# dic_deska.net
KiCad netlist of a schematic drawn in EAGLE
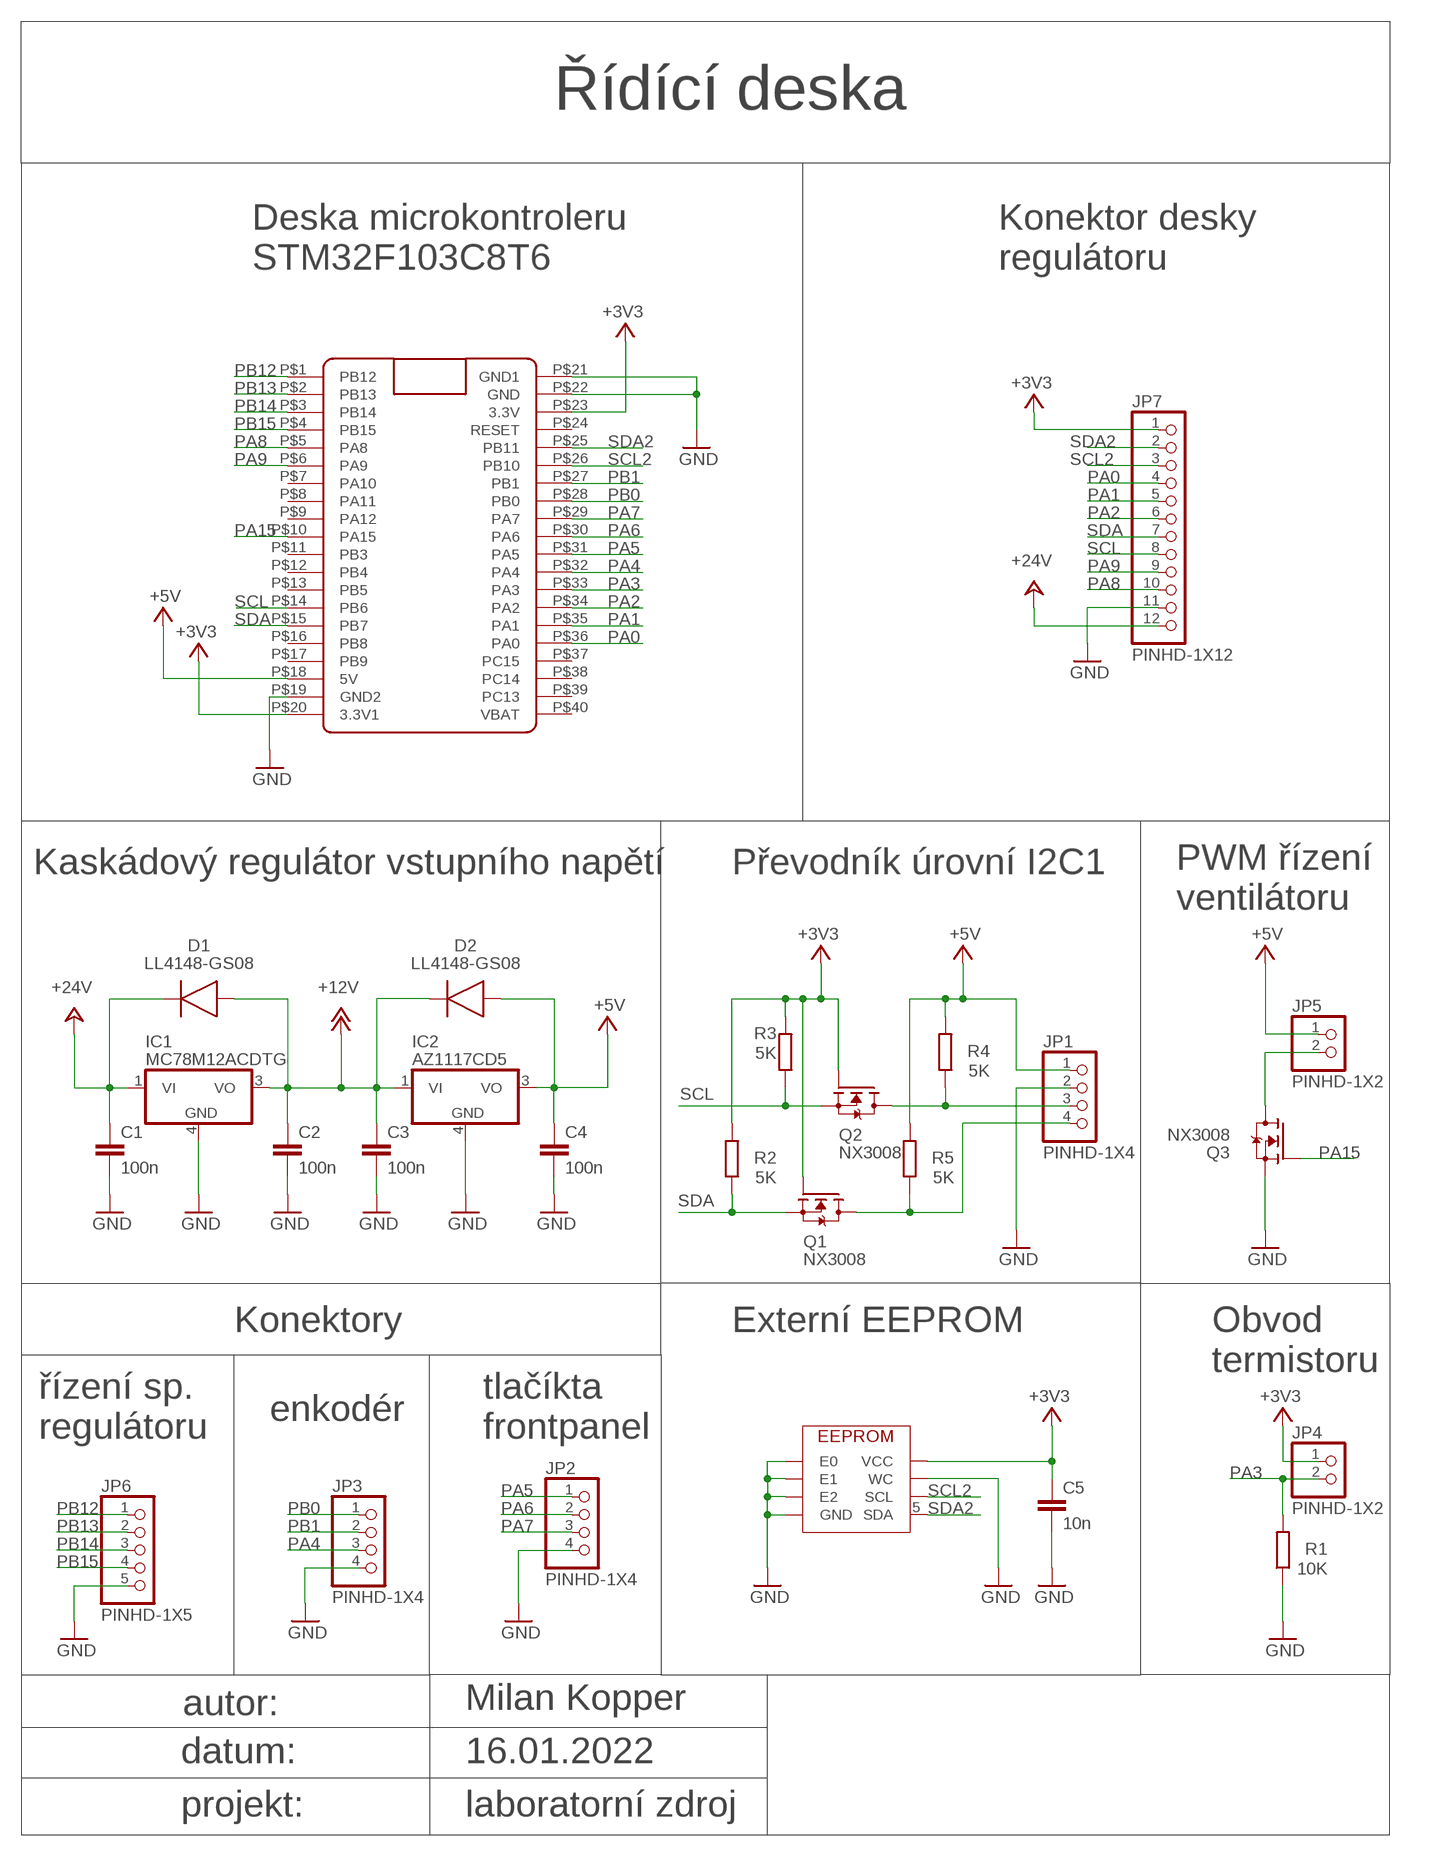
[diagram p0: schematic, sheet 1]

(export (version "E")
  (design (tool "Eeschema 10.0.6"))
  (components
    (comp (ref "C1")
      (value "100n")
      (footprint "eagle-import:C0805")
      (libsource (lib "eagle-import") (part "C-EUC0805"))
    )
    (comp (ref "C2")
      (value "100n")
      (footprint "eagle-import:C0805")
      (libsource (lib "eagle-import") (part "C-EUC0805"))
    )
    (comp (ref "C3")
      (value "100n")
      (footprint "eagle-import:C0805")
      (libsource (lib "eagle-import") (part "C-EUC0805"))
    )
    (comp (ref "C4")
      (value "100n")
      (footprint "eagle-import:C0805")
      (libsource (lib "eagle-import") (part "C-EUC0805"))
    )
    (comp (ref "C5")
      (value "10n")
      (footprint "eagle-import:C0805")
      (libsource (lib "eagle-import") (part "C-EUC0805"))
    )
    (comp (ref "D1")
      (value "LL4148-GS08")
      (footprint "eagle-import:DIOMELF3516")
      (fields (field (name "MANUFACTURER") "Vishay Semiconductor Diodes Division "))
      (libsource (lib "eagle-import") (part "DIODE__SOD-80LL4148-GS08"))
    )
    (comp (ref "D2")
      (value "LL4148-GS08")
      (footprint "eagle-import:DIOMELF3516")
      (fields (field (name "MANUFACTURER") "Vishay Semiconductor Diodes Division "))
      (libsource (lib "eagle-import") (part "DIODE__SOD-80LL4148-GS08"))
    )
    (comp (ref "IC1")
      (value "MC78M12ACDTG")
      (footprint "eagle-import:DPACK_3")
      (libsource (lib "eagle-import") (part "MC78M12BDTG"))
    )
    (comp (ref "IC2")
      (value "AZ1117CD5")
      (footprint "eagle-import:DPACK_3")
      (libsource (lib "eagle-import") (part "MC78M05CDTG"))
    )
    (comp (ref "JP1")
      (value "PINHD-1X4")
      (footprint "eagle-import:1X04")
      (libsource (lib "eagle-import") (part "PINHD-1X4"))
    )
    (comp (ref "JP2")
      (value "PINHD-1X4")
      (footprint "eagle-import:1X04")
      (libsource (lib "eagle-import") (part "PINHD-1X4"))
    )
    (comp (ref "JP3")
      (value "PINHD-1X4")
      (footprint "eagle-import:1X04")
      (libsource (lib "eagle-import") (part "PINHD-1X4"))
    )
    (comp (ref "JP4")
      (value "PINHD-1X2")
      (footprint "eagle-import:1X02")
      (libsource (lib "eagle-import") (part "PINHD-1X2"))
    )
    (comp (ref "JP5")
      (value "PINHD-1X2")
      (footprint "eagle-import:1X02")
      (libsource (lib "eagle-import") (part "PINHD-1X2"))
    )
    (comp (ref "JP6")
      (value "PINHD-1X5")
      (footprint "eagle-import:1X05")
      (libsource (lib "eagle-import") (part "PINHD-1X5"))
    )
    (comp (ref "JP7")
      (value "PINHD-1X12")
      (footprint "eagle-import:1X12")
      (libsource (lib "eagle-import") (part "PINHD-1X12"))
    )
    (comp (ref "Q1")
      (value "NX3008")
      (footprint "eagle-import:SOT95P240X110-3N")
      (libsource (lib "eagle-import") (part "NX3008"))
    )
    (comp (ref "Q2")
      (value "NX3008")
      (footprint "eagle-import:SOT95P240X110-3N")
      (libsource (lib "eagle-import") (part "NX3008"))
    )
    (comp (ref "Q3")
      (value "NX3008")
      (footprint "eagle-import:SOT95P240X110-3N")
      (libsource (lib "eagle-import") (part "NX3008"))
    )
    (comp (ref "R1")
      (value "10K")
      (footprint "eagle-import:R0805")
      (libsource (lib "eagle-import") (part "R-EU_R0805"))
    )
    (comp (ref "R2")
      (value "5K")
      (footprint "eagle-import:R0805")
      (libsource (lib "eagle-import") (part "R-EU_R0805"))
    )
    (comp (ref "R3")
      (value "5K")
      (footprint "eagle-import:R0805")
      (libsource (lib "eagle-import") (part "R-EU_R0805"))
    )
    (comp (ref "R4")
      (value "5K")
      (footprint "eagle-import:R0805")
      (libsource (lib "eagle-import") (part "R-EU_R0805"))
    )
    (comp (ref "R5")
      (value "5K")
      (footprint "eagle-import:R0805")
      (libsource (lib "eagle-import") (part "R-EU_R0805"))
    )
    (comp (ref "U$1")
      (value "BLUE_PILL")
      (footprint "eagle-import:BLUE_PILL")
      (libsource (lib "eagle-import") (part "BLUE_PILL"))
    )
    (comp (ref "U$2")
      (value "M24CXX")
      (footprint "eagle-import:SO8")
      (libsource (lib "eagle-import") (part "M24CXX"))
    )
  )
  (nets
    (net (code "1") (name "+3V3") (class "Default")
      (node (ref "C5") (pin "1") (pinfunction "1_1") (pintype "passive"))
      (node (ref "JP4") (pin "1") (pinfunction "1_1") (pintype "passive"))
      (node (ref "JP7") (pin "1") (pinfunction "1_1") (pintype "passive"))
      (node (ref "Q1") (pin "1") (pinfunction "G_1") (pintype "passive"))
      (node (ref "Q2") (pin "1") (pinfunction "G_1") (pintype "passive"))
      (node (ref "R2") (pin "2") (pinfunction "2_2") (pintype "passive"))
      (node (ref "R3") (pin "2") (pinfunction "2_2") (pintype "passive"))
      (node (ref "U$1") (pin "P$20") (pinfunction "3.3V1_P$20") (pintype "bidirectional"))
      (node (ref "U$1") (pin "P$23") (pinfunction "3.3V_P$23") (pintype "bidirectional"))
      (node (ref "U$2") (pin "8") (pinfunction "VCC_8") (pintype "bidirectional"))
    )
    (net (code "2") (name "+5V") (class "Default")
      (node (ref "C4") (pin "1") (pinfunction "1_1") (pintype "passive"))
      (node (ref "D2") (pin "2") (pinfunction "A_2") (pintype "passive"))
      (node (ref "IC2") (pin "3") (pinfunction "VO_3") (pintype "passive"))
      (node (ref "JP1") (pin "1") (pinfunction "1_1") (pintype "passive"))
      (node (ref "JP5") (pin "1") (pinfunction "1_1") (pintype "passive"))
      (node (ref "R4") (pin "2") (pinfunction "2_2") (pintype "passive"))
      (node (ref "R5") (pin "2") (pinfunction "2_2") (pintype "passive"))
      (node (ref "U$1") (pin "P$18") (pinfunction "5V_P$18") (pintype "bidirectional"))
    )
    (net (code "3") (name "+12V") (class "Default")
      (node (ref "C2") (pin "1") (pinfunction "1_1") (pintype "passive"))
      (node (ref "C3") (pin "1") (pinfunction "1_1") (pintype "passive"))
      (node (ref "D1") (pin "2") (pinfunction "A_2") (pintype "passive"))
      (node (ref "D2") (pin "1") (pinfunction "C_1") (pintype "passive"))
      (node (ref "IC1") (pin "3") (pinfunction "VO_3") (pintype "passive"))
      (node (ref "IC2") (pin "1") (pinfunction "VI_1") (pintype "input"))
    )
    (net (code "4") (name "+24V") (class "Default")
      (node (ref "C1") (pin "1") (pinfunction "1_1") (pintype "passive"))
      (node (ref "D1") (pin "1") (pinfunction "C_1") (pintype "passive"))
      (node (ref "IC1") (pin "1") (pinfunction "VI_1") (pintype "input"))
      (node (ref "JP7") (pin "12") (pinfunction "12_12") (pintype "passive"))
    )
    (net (code "5") (name "/PA0") (class "Default")
      (node (ref "JP7") (pin "4") (pinfunction "4_4") (pintype "passive"))
      (node (ref "U$1") (pin "P$36") (pinfunction "PA0_P$36") (pintype "bidirectional"))
    )
    (net (code "6") (name "/PA1") (class "Default")
      (node (ref "JP7") (pin "5") (pinfunction "5_5") (pintype "passive"))
      (node (ref "U$1") (pin "P$35") (pinfunction "PA1_P$35") (pintype "bidirectional"))
    )
    (net (code "7") (name "/PA2") (class "Default")
      (node (ref "JP7") (pin "6") (pinfunction "6_6") (pintype "passive"))
      (node (ref "U$1") (pin "P$34") (pinfunction "PA2_P$34") (pintype "bidirectional"))
    )
    (net (code "8") (name "/PA3") (class "Default")
      (node (ref "JP4") (pin "2") (pinfunction "2_2") (pintype "passive"))
      (node (ref "R1") (pin "2") (pinfunction "2_2") (pintype "passive"))
      (node (ref "U$1") (pin "P$33") (pinfunction "PA3_P$33") (pintype "bidirectional"))
    )
    (net (code "9") (name "/PA4") (class "Default")
      (node (ref "JP3") (pin "3") (pinfunction "3_3") (pintype "passive"))
      (node (ref "U$1") (pin "P$32") (pinfunction "PA4_P$32") (pintype "bidirectional"))
    )
    (net (code "10") (name "/PA5") (class "Default")
      (node (ref "JP2") (pin "1") (pinfunction "1_1") (pintype "passive"))
      (node (ref "U$1") (pin "P$31") (pinfunction "PA5_P$31") (pintype "bidirectional"))
    )
    (net (code "11") (name "/PA6") (class "Default")
      (node (ref "JP2") (pin "2") (pinfunction "2_2") (pintype "passive"))
      (node (ref "U$1") (pin "P$30") (pinfunction "PA6_P$30") (pintype "bidirectional"))
    )
    (net (code "12") (name "/PA7") (class "Default")
      (node (ref "JP2") (pin "3") (pinfunction "3_3") (pintype "passive"))
      (node (ref "U$1") (pin "P$29") (pinfunction "PA7_P$29") (pintype "bidirectional"))
    )
    (net (code "13") (name "/PA8") (class "Default")
      (node (ref "JP7") (pin "10") (pinfunction "10_10") (pintype "passive"))
      (node (ref "U$1") (pin "P$5") (pinfunction "PA8_P$5") (pintype "bidirectional"))
    )
    (net (code "14") (name "/PA9") (class "Default")
      (node (ref "JP7") (pin "9") (pinfunction "9_9") (pintype "passive"))
      (node (ref "U$1") (pin "P$6") (pinfunction "PA9_P$6") (pintype "bidirectional"))
    )
    (net (code "15") (name "/PA15") (class "Default")
      (node (ref "Q3") (pin "1") (pinfunction "G_1") (pintype "passive"))
      (node (ref "U$1") (pin "P$10") (pinfunction "PA15_P$10") (pintype "bidirectional"))
    )
    (net (code "16") (name "/PB0") (class "Default")
      (node (ref "JP3") (pin "1") (pinfunction "1_1") (pintype "passive"))
      (node (ref "U$1") (pin "P$28") (pinfunction "PB0_P$28") (pintype "bidirectional"))
    )
    (net (code "17") (name "/PB1") (class "Default")
      (node (ref "JP3") (pin "2") (pinfunction "2_2") (pintype "passive"))
      (node (ref "U$1") (pin "P$27") (pinfunction "PB1_P$27") (pintype "bidirectional"))
    )
    (net (code "18") (name "/PB12") (class "Default")
      (node (ref "JP6") (pin "1") (pinfunction "1_1") (pintype "passive"))
      (node (ref "U$1") (pin "P$1") (pinfunction "PB12_P$1") (pintype "bidirectional"))
    )
    (net (code "19") (name "/PB13") (class "Default")
      (node (ref "JP6") (pin "2") (pinfunction "2_2") (pintype "passive"))
      (node (ref "U$1") (pin "P$2") (pinfunction "PB13_P$2") (pintype "bidirectional"))
    )
    (net (code "20") (name "/PB14") (class "Default")
      (node (ref "JP6") (pin "3") (pinfunction "3_3") (pintype "passive"))
      (node (ref "U$1") (pin "P$3") (pinfunction "PB14_P$3") (pintype "bidirectional"))
    )
    (net (code "21") (name "/PB15") (class "Default")
      (node (ref "JP6") (pin "4") (pinfunction "4_4") (pintype "passive"))
      (node (ref "U$1") (pin "P$4") (pinfunction "PB15_P$4") (pintype "bidirectional"))
    )
    (net (code "22") (name "/SCL") (class "Default")
      (node (ref "JP7") (pin "8") (pinfunction "8_8") (pintype "passive"))
      (node (ref "Q2") (pin "2") (pinfunction "S_2") (pintype "passive"))
      (node (ref "R3") (pin "1") (pinfunction "1_1") (pintype "passive"))
      (node (ref "U$1") (pin "P$14") (pinfunction "PB6_P$14") (pintype "bidirectional"))
    )
    (net (code "23") (name "/SCL2") (class "Default")
      (node (ref "JP7") (pin "3") (pinfunction "3_3") (pintype "passive"))
      (node (ref "U$1") (pin "P$26") (pinfunction "PB10_P$26") (pintype "bidirectional"))
      (node (ref "U$2") (pin "6") (pinfunction "SCL_6") (pintype "bidirectional"))
    )
    (net (code "24") (name "/SDA") (class "Default")
      (node (ref "JP7") (pin "7") (pinfunction "7_7") (pintype "passive"))
      (node (ref "Q1") (pin "2") (pinfunction "S_2") (pintype "passive"))
      (node (ref "R2") (pin "1") (pinfunction "1_1") (pintype "passive"))
      (node (ref "U$1") (pin "P$15") (pinfunction "PB7_P$15") (pintype "bidirectional"))
    )
    (net (code "25") (name "/SDA2") (class "Default")
      (node (ref "JP7") (pin "2") (pinfunction "2_2") (pintype "passive"))
      (node (ref "U$1") (pin "P$25") (pinfunction "PB11_P$25") (pintype "bidirectional"))
      (node (ref "U$2") (pin "5") (pinfunction "SDA_5") (pintype "bidirectional"))
    )
    (net (code "26") (name "GND") (class "Default")
      (node (ref "C1") (pin "2") (pinfunction "2_2") (pintype "passive"))
      (node (ref "C2") (pin "2") (pinfunction "2_2") (pintype "passive"))
      (node (ref "C3") (pin "2") (pinfunction "2_2") (pintype "passive"))
      (node (ref "C4") (pin "2") (pinfunction "2_2") (pintype "passive"))
      (node (ref "C5") (pin "2") (pinfunction "2_2") (pintype "passive"))
      (node (ref "IC1") (pin "4") (pinfunction "GND_4") (pintype "passive"))
      (node (ref "IC2") (pin "4") (pinfunction "GND_4") (pintype "passive"))
      (node (ref "JP1") (pin "2") (pinfunction "2_2") (pintype "passive"))
      (node (ref "JP2") (pin "4") (pinfunction "4_4") (pintype "passive"))
      (node (ref "JP3") (pin "4") (pinfunction "4_4") (pintype "passive"))
      (node (ref "JP6") (pin "5") (pinfunction "5_5") (pintype "passive"))
      (node (ref "JP7") (pin "11") (pinfunction "11_11") (pintype "passive"))
      (node (ref "Q3") (pin "2") (pinfunction "S_2") (pintype "passive"))
      (node (ref "R1") (pin "1") (pinfunction "1_1") (pintype "passive"))
      (node (ref "U$1") (pin "P$19") (pinfunction "GND2_P$19") (pintype "bidirectional"))
      (node (ref "U$1") (pin "P$21") (pinfunction "GND1_P$21") (pintype "power_in"))
      (node (ref "U$1") (pin "P$22") (pinfunction "GND_P$22") (pintype "bidirectional"))
      (node (ref "U$2") (pin "1") (pinfunction "E0_1") (pintype "bidirectional"))
      (node (ref "U$2") (pin "2") (pinfunction "E1_2") (pintype "bidirectional"))
      (node (ref "U$2") (pin "3") (pinfunction "E2_3") (pintype "bidirectional"))
      (node (ref "U$2") (pin "4") (pinfunction "GND_4") (pintype "bidirectional"))
      (node (ref "U$2") (pin "7") (pinfunction "WC_7") (pintype "bidirectional"))
    )
    (net (code "27") (name "Net-(Q1-D)") (class "Default")
      (node (ref "JP1") (pin "4") (pinfunction "4_4") (pintype "passive"))
      (node (ref "Q1") (pin "3") (pinfunction "D_3") (pintype "passive"))
      (node (ref "R5") (pin "1") (pinfunction "1_1") (pintype "passive"))
    )
    (net (code "28") (name "Net-(Q2-D)") (class "Default")
      (node (ref "JP1") (pin "3") (pinfunction "3_3") (pintype "passive"))
      (node (ref "Q2") (pin "3") (pinfunction "D_3") (pintype "passive"))
      (node (ref "R4") (pin "1") (pinfunction "1_1") (pintype "passive"))
    )
    (net (code "29") (name "Net-(Q3-D)") (class "Default")
      (node (ref "JP5") (pin "2") (pinfunction "2_2") (pintype "passive"))
      (node (ref "Q3") (pin "3") (pinfunction "D_3") (pintype "passive"))
    )
    (net (code "30") (name "unconnected-(U$1-PA10-PadP$7)") (class "Default")
      (node (ref "U$1") (pin "P$7") (pinfunction "PA10_P$7") (pintype "bidirectional"))
    )
    (net (code "31") (name "unconnected-(U$1-PA11-PadP$8)") (class "Default")
      (node (ref "U$1") (pin "P$8") (pinfunction "PA11_P$8") (pintype "bidirectional"))
    )
    (net (code "32") (name "unconnected-(U$1-PA12-PadP$9)") (class "Default")
      (node (ref "U$1") (pin "P$9") (pinfunction "PA12_P$9") (pintype "bidirectional"))
    )
    (net (code "33") (name "unconnected-(U$1-PB3-PadP$11)") (class "Default")
      (node (ref "U$1") (pin "P$11") (pinfunction "PB3_P$11") (pintype "bidirectional"))
    )
    (net (code "34") (name "unconnected-(U$1-PB4-PadP$12)") (class "Default")
      (node (ref "U$1") (pin "P$12") (pinfunction "PB4_P$12") (pintype "bidirectional"))
    )
    (net (code "35") (name "unconnected-(U$1-PB5-PadP$13)") (class "Default")
      (node (ref "U$1") (pin "P$13") (pinfunction "PB5_P$13") (pintype "bidirectional"))
    )
    (net (code "36") (name "unconnected-(U$1-PB8-PadP$16)") (class "Default")
      (node (ref "U$1") (pin "P$16") (pinfunction "PB8_P$16") (pintype "bidirectional"))
    )
    (net (code "37") (name "unconnected-(U$1-PB9-PadP$17)") (class "Default")
      (node (ref "U$1") (pin "P$17") (pinfunction "PB9_P$17") (pintype "bidirectional"))
    )
    (net (code "38") (name "unconnected-(U$1-PC13-PadP$39)") (class "Default")
      (node (ref "U$1") (pin "P$39") (pinfunction "PC13_P$39") (pintype "bidirectional"))
    )
    (net (code "39") (name "unconnected-(U$1-PC14-PadP$38)") (class "Default")
      (node (ref "U$1") (pin "P$38") (pinfunction "PC14_P$38") (pintype "bidirectional"))
    )
    (net (code "40") (name "unconnected-(U$1-PC15-PadP$37)") (class "Default")
      (node (ref "U$1") (pin "P$37") (pinfunction "PC15_P$37") (pintype "bidirectional"))
    )
    (net (code "41") (name "unconnected-(U$1-RESET-PadP$24)") (class "Default")
      (node (ref "U$1") (pin "P$24") (pinfunction "RESET_P$24") (pintype "bidirectional"))
    )
    (net (code "42") (name "unconnected-(U$1-VBAT-PadP$40)") (class "Default")
      (node (ref "U$1") (pin "P$40") (pinfunction "VBAT_P$40") (pintype "bidirectional"))
    )
  )
)
